# No_Transistor_LED_INV.net
KiCad netlist of a schematic drawn in Altium Designer
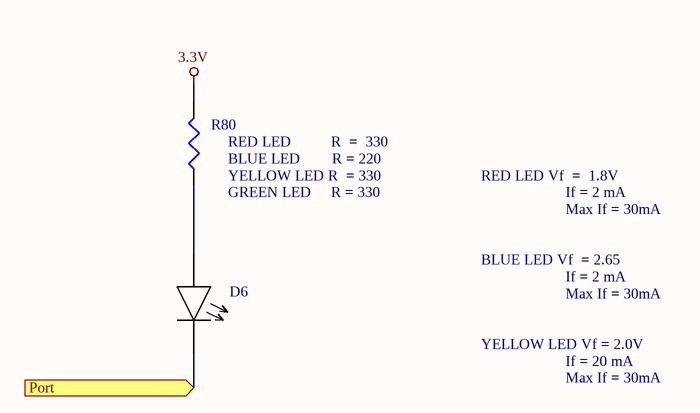
[diagram p0: No_Transistor_LED_INV.SchDoc]

(export (version "E")
  (design (tool "Eeschema 10.0.6"))
  (components
    (comp (ref "D6")
      (value "LED_R")
      (footprint "0402 footprint")
      (libsource (lib "AvionicsParts") (part "LED_R"))
    )
    (comp (ref "R80")
      (value "Res3")
      (description "Resistor")
      (fields (field (name "PUBLISHER") "Altium Limited"))
      (libsource (lib "Miscellaneous Devices") (part "Res3"))
    )
  )
  (nets
    (net (code "1") (name "/Port") (class "Default")
      (node (ref "D6") (pin "2") (pinfunction "2_2") (pintype "passive"))
    )
    (net (code "2") (name "3.3V") (class "Default")
      (node (ref "R80") (pin "2") (pinfunction "2_2") (pintype "passive"))
    )
    (net (code "3") (name "Net-(D6-Pad1)") (class "Default")
      (node (ref "D6") (pin "1") (pinfunction "1_1") (pintype "passive"))
      (node (ref "R80") (pin "1") (pinfunction "1_1") (pintype "passive"))
    )
  )
)
